# HAE_Power_Protection.net
KiCad netlist of a schematic drawn in Altium Designer
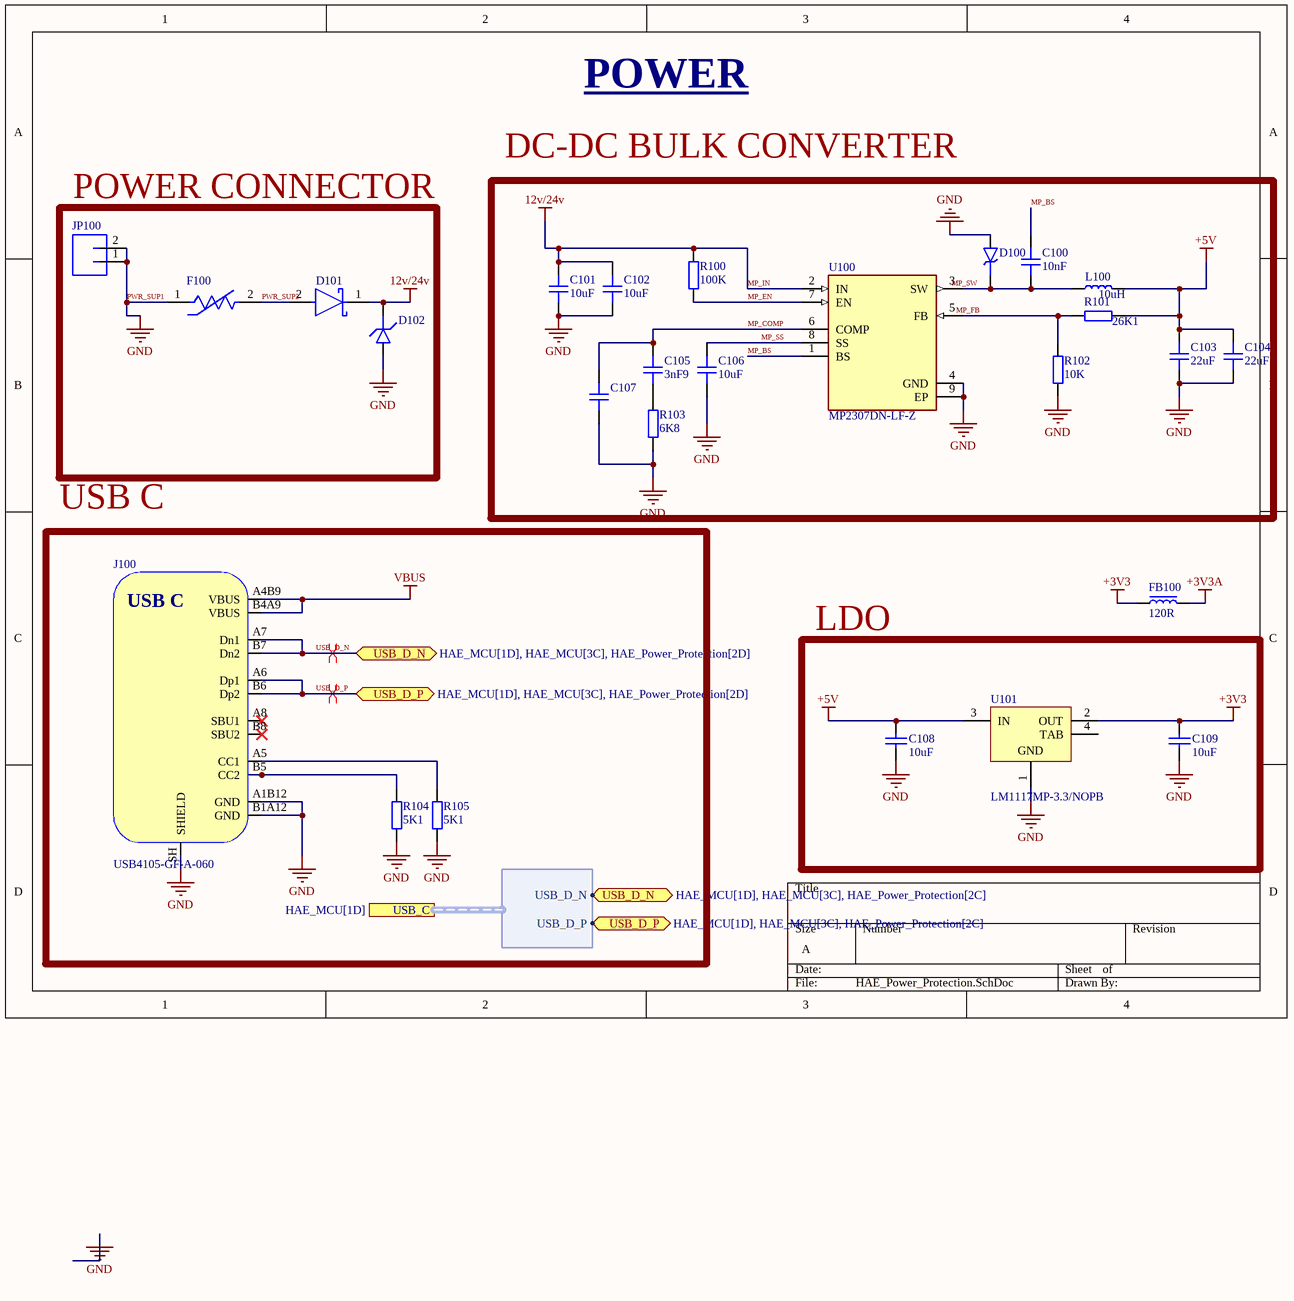
[diagram p0: HAE_Power_Protection.SchDoc]

(export (version "E")
  (design (tool "Eeschema 10.0.6"))
  (components
    (comp (ref "C100")
      (value "10nF")
      (footprint "CAP_0603")
      (description "Capacitor SMD 0603")
      (libsource (lib "PhilsLab_Library") (part "CAP_0603"))
    )
    (comp (ref "C101")
      (value "10uF")
      (footprint "CAP_0603")
      (description "Capacitor SMD 0603")
      (libsource (lib "PhilsLab_Library") (part "CAP_0603"))
    )
    (comp (ref "C102")
      (value "10uF")
      (footprint "CAP_0603")
      (description "Capacitor SMD 0603")
      (libsource (lib "PhilsLab_Library") (part "CAP_0603"))
    )
    (comp (ref "C103")
      (value "22uF")
      (footprint "CAP_0603")
      (description "Capacitor SMD 0603")
      (libsource (lib "PhilsLab_Library") (part "CAP_0603"))
    )
    (comp (ref "C104")
      (value "22uF")
      (footprint "CAP_0603")
      (description "Capacitor SMD 0603")
      (libsource (lib "PhilsLab_Library") (part "CAP_0603"))
    )
    (comp (ref "C105")
      (value "3nF9")
      (footprint "CAP_0603")
      (description "Capacitor SMD 0603")
      (libsource (lib "PhilsLab_Library") (part "CAP_0603"))
    )
    (comp (ref "C106")
      (value "10uF")
      (footprint "CAP_0603")
      (description "Capacitor SMD 0603")
      (libsource (lib "PhilsLab_Library") (part "CAP_0603"))
    )
    (comp (ref "C107")
      (value "10uF")
      (footprint "CAP_0603")
      (description "Capacitor SMD 0603")
      (libsource (lib "PhilsLab_Library") (part "CAP_0603"))
    )
    (comp (ref "C108")
      (value "10uF")
      (footprint "CAPC2014X60X15NL20")
      (description "TACH106M010XTA")
      (fields (field (name "MANUFACTURER") "AVX Interconnect / Elco"))
      (libsource (lib "Altium Content Vault") (part "CAP"))
    )
    (comp (ref "C109")
      (value "10uF")
      (footprint "CAPC2014X60X15NL20")
      (description "TACH106M010XTA")
      (fields (field (name "MANUFACTURER") "AVX Interconnect / Elco"))
      (libsource (lib "Altium Content Vault") (part "CAP"))
    )
    (comp (ref "D100")
      (value "D_ZENER_SOD_323")
      (footprint "SOD-323")
      (description "Diode Zener SMD SOD-323")
      (libsource (lib "PhilsLab_Library") (part "D_ZENER_SOD_323"))
    )
    (comp (ref "D101")
      (value "SS34-E3/9AT")
      (footprint "FP-SMC-MFG")
      (description "DIODE SCHOTTKY 40V 3A DO214AB")
      (libsource (lib "Altium Content Vault") (part "c1678fac7984e62e0809fbf79c06691"))
    )
    (comp (ref "D102")
      (value "D_TVS_0402")
      (footprint "D_0402")
      (description "Diode TVS / ESD 0402")
      (libsource (lib "PhilsLab_Library") (part "D_TVS_0402"))
    )
    (comp (ref "F100")
      (value "MF-PSMF020X-2")
      (footprint "FP-MF-PSMF-MFG")
      (description "PTC RESET FUSE 9V 200MA 0805")
      (fields
        (field (name "MANUFACTURER") "Bourns")
        (field (name "OCTOPART") "https://octopart.com/mf-psmf020x-2-bourns-7483437")
      )
      (libsource (lib "Altium Content Vault") (part "3b148a6ebabc5fb4d708a66c052d352"))
    )
    (comp (ref "FB100")
      (value "120R")
      (footprint "FB_0603")
      (description "Ferrite Bead SMD 0603")
      (libsource (lib "Schematic-Lib-PhilsLab") (part "FB_0603"))
    )
    (comp (ref "J100")
      (value "USB4105-GF-A-060")
      (footprint "USB4105-GF-A-060")
      (description "USB Connector Type C SMT 12 Pin")
      (fields (field (name "MANUFACTURER") "GCT"))
      (libsource (lib "PhilsLab_Library") (part "USB4105-GF-A-060"))
    )
    (comp (ref "JP100")
      (value "MOLEX_MICROFIT_2_SMD_HORZ")
      (footprint "MOLEX-MICROFIT-2-SMD-HORZ")
      (fields (field (name "MANUFACTURER") "Molex") (field (name "PARTNUMBER") "43650-0212"))
      (libsource (lib "HAE_Schlib1") (part "MOLEX_MICROFIT_2_SMD_HORZ"))
    )
    (comp (ref "L100")
      (value "10uH")
      (footprint "IND_0603")
      (description "Inductor SMD 0603")
      (libsource (lib "PhilsLab_Library") (part "IND_0603"))
    )
    (comp (ref "R100")
      (value "100K")
      (footprint "RES_0603")
      (description "Resistor SMD 0603")
      (libsource (lib "PhilsLab_Library") (part "RES_0603"))
    )
    (comp (ref "R101")
      (value "26K1")
      (footprint "RES_0603")
      (description "Resistor SMD 0603")
      (libsource (lib "PhilsLab_Library") (part "RES_0603"))
    )
    (comp (ref "R102")
      (value "10K")
      (footprint "RES_0603")
      (description "Resistor SMD 0603")
      (libsource (lib "PhilsLab_Library") (part "RES_0603"))
    )
    (comp (ref "R103")
      (value "6K8")
      (footprint "RES_0603")
      (description "Resistor SMD 0603")
      (libsource (lib "PhilsLab_Library") (part "RES_0603"))
    )
    (comp (ref "R104")
      (value "5K1")
      (footprint "RES_0402")
      (description "Resistor SMD 0402")
      (libsource (lib "PhilsLab_Library") (part "RES_0402"))
    )
    (comp (ref "R105")
      (value "5K1")
      (footprint "RES_0402")
      (description "Resistor SMD 0402")
      (libsource (lib "PhilsLab_Library") (part "RES_0402"))
    )
    (comp (ref "U100")
      (value "MP2307DN-LF-Z")
      (footprint "SOIC127P600X170-9N")
      (fields (field (name "MF") "Monolithic Power"))
      (libsource (lib "HAE_Schlib1") (part "MP2307DN-LF-Z"))
    )
    (comp (ref "U101")
      (value "LM1117MP-3.3/NOPB")
      (footprint "DCY0004A_L")
      (description "800mA Low-Dropout Linear Regulator, 4-pin SOT-223, Pb-Free")
      (fields (field (name "MANUFACTURER") "Texas Instruments"))
      (libsource (lib "Altium Content Vault") (part "PM-REG-LM1086-SOT4"))
    )
  )
  (nets
    (net (code "2") (name "+3V3") (class "Default")
      (node (ref "C109") (pin "2") (pinfunction "2_2") (pintype "passive"))
      (node (ref "FB100") (pin "1") (pinfunction "1_1") (pintype "passive"))
      (node (ref "U101") (pin "2") (pinfunction "OUT_2") (pintype "power_in"))
    )
    (net (code "3") (name "+3V3A") (class "Default")
      (node (ref "FB100") (pin "2") (pinfunction "2_2") (pintype "passive"))
    )
    (net (code "4") (name "+5V") (class "Default")
      (node (ref "C103") (pin "2") (pinfunction "2_2") (pintype "passive"))
      (node (ref "C104") (pin "2") (pinfunction "2_2") (pintype "passive"))
      (node (ref "C108") (pin "2") (pinfunction "2_2") (pintype "passive"))
      (node (ref "L100") (pin "2") (pinfunction "2_2") (pintype "passive"))
      (node (ref "R101") (pin "1") (pinfunction "1_1") (pintype "passive"))
      (node (ref "U101") (pin "3") (pinfunction "IN_3") (pintype "power_in"))
    )
    (net (code "5") (name "/MP_BS") (class "Default")
      (node (ref "C100") (pin "1") (pinfunction "1_1") (pintype "passive"))
      (node (ref "U100") (pin "1") (pinfunction "BS_1") (pintype "passive"))
    )
    (net (code "6") (name "/MP_COMP") (class "Default")
      (node (ref "C105") (pin "2") (pinfunction "2_2") (pintype "passive"))
      (node (ref "C107") (pin "2") (pinfunction "2_2") (pintype "passive"))
      (node (ref "U100") (pin "6") (pinfunction "COMP_6") (pintype "passive"))
    )
    (net (code "7") (name "/MP_EN") (class "Default")
      (node (ref "R100") (pin "1") (pinfunction "1_1") (pintype "passive"))
      (node (ref "U100") (pin "7") (pinfunction "EN_7") (pintype "input"))
    )
    (net (code "8") (name "/MP_FB") (class "Default")
      (node (ref "R101") (pin "2") (pinfunction "2_2") (pintype "passive"))
      (node (ref "R102") (pin "2") (pinfunction "2_2") (pintype "passive"))
      (node (ref "U100") (pin "5") (pinfunction "FB_5") (pintype "input"))
    )
    (net (code "9") (name "/MP_SS") (class "Default")
      (node (ref "C106") (pin "2") (pinfunction "2_2") (pintype "passive"))
      (node (ref "U100") (pin "8") (pinfunction "SS_8") (pintype "passive"))
    )
    (net (code "10") (name "/MP_SW") (class "Default")
      (node (ref "C100") (pin "2") (pinfunction "2_2") (pintype "passive"))
      (node (ref "D100") (pin "K") (pinfunction "K_K") (pintype "passive"))
      (node (ref "L100") (pin "1") (pinfunction "1_1") (pintype "passive"))
      (node (ref "U100") (pin "3") (pinfunction "SW_3") (pintype "output"))
    )
    (net (code "11") (name "/PWR_SUP2") (class "Default")
      (node (ref "D101") (pin "2") (pinfunction "A_2") (pintype "passive"))
      (node (ref "F100") (pin "2") (pinfunction "2_2") (pintype "passive"))
    )
    (net (code "12") (name "/USB_D_N") (class "Default")
      (node (ref "J100") (pin "A7") (pinfunction "Dn1_A7") (pintype "passive"))
      (node (ref "J100") (pin "B7") (pinfunction "Dn2_B7") (pintype "passive"))
    )
    (net (code "13") (name "/USB_D_P") (class "Default")
      (node (ref "J100") (pin "A6") (pinfunction "Dp1_A6") (pintype "passive"))
      (node (ref "J100") (pin "B6") (pinfunction "Dp2_B6") (pintype "passive"))
    )
    (net (code "15") (name "12v{slash}24v") (class "Default")
      (node (ref "C101") (pin "2") (pinfunction "2_2") (pintype "passive"))
      (node (ref "C102") (pin "2") (pinfunction "2_2") (pintype "passive"))
      (node (ref "D101") (pin "1") (pinfunction "C_1") (pintype "passive"))
      (node (ref "D102") (pin "K") (pinfunction "K_K") (pintype "passive"))
      (node (ref "R100") (pin "2") (pinfunction "2_2") (pintype "passive"))
      (node (ref "U100") (pin "2") (pinfunction "IN_2") (pintype "input"))
    )
    (net (code "16") (name "GND") (class "Default")
      (node (ref "C101") (pin "1") (pinfunction "1_1") (pintype "passive"))
      (node (ref "C102") (pin "1") (pinfunction "1_1") (pintype "passive"))
      (node (ref "C103") (pin "1") (pinfunction "1_1") (pintype "passive"))
      (node (ref "C104") (pin "1") (pinfunction "1_1") (pintype "passive"))
      (node (ref "C106") (pin "1") (pinfunction "1_1") (pintype "passive"))
      (node (ref "C107") (pin "1") (pinfunction "1_1") (pintype "passive"))
      (node (ref "C108") (pin "1") (pinfunction "1_1") (pintype "passive"))
      (node (ref "C109") (pin "1") (pinfunction "1_1") (pintype "passive"))
      (node (ref "D100") (pin "A") (pinfunction "A_A") (pintype "passive"))
      (node (ref "D102") (pin "A") (pinfunction "A_A") (pintype "passive"))
      (node (ref "F100") (pin "1") (pinfunction "1_1") (pintype "passive"))
      (node (ref "J100") (pin "A1B12") (pinfunction "GND_A1B12") (pintype "passive"))
      (node (ref "J100") (pin "B1A12") (pinfunction "GND_B1A12") (pintype "passive"))
      (node (ref "J100") (pin "SH") (pinfunction "SHIELD_SH") (pintype "passive"))
      (node (ref "JP100") (pin "1") (pinfunction "1_1") (pintype "passive"))
      (node (ref "JP100") (pin "2") (pinfunction "2_2") (pintype "passive"))
      (node (ref "R102") (pin "1") (pinfunction "1_1") (pintype "passive"))
      (node (ref "R103") (pin "1") (pinfunction "1_1") (pintype "passive"))
      (node (ref "R104") (pin "1") (pinfunction "1_1") (pintype "passive"))
      (node (ref "R105") (pin "1") (pinfunction "1_1") (pintype "passive"))
      (node (ref "U100") (pin "4") (pinfunction "GND_4") (pintype "power_in"))
      (node (ref "U100") (pin "9") (pinfunction "EP_9") (pintype "power_in"))
      (node (ref "U101") (pin "1") (pinfunction "GND_1") (pintype "power_in"))
    )
    (net (code "17") (name "Net-(C105-Pad1)") (class "Default")
      (node (ref "C105") (pin "1") (pinfunction "1_1") (pintype "passive"))
      (node (ref "R103") (pin "2") (pinfunction "2_2") (pintype "passive"))
    )
    (net (code "18") (name "Net-(J100-CC1)") (class "Default")
      (node (ref "J100") (pin "A5") (pinfunction "CC1_A5") (pintype "passive"))
      (node (ref "R105") (pin "2") (pinfunction "2_2") (pintype "passive"))
    )
    (net (code "19") (name "Net-(J100-CC2)") (class "Default")
      (node (ref "J100") (pin "B5") (pinfunction "CC2_B5") (pintype "passive"))
      (node (ref "R104") (pin "2") (pinfunction "2_2") (pintype "passive"))
    )
    (net (code "20") (name "VBUS") (class "Default")
      (node (ref "J100") (pin "A4B9") (pinfunction "VBUS_A4B9") (pintype "passive"))
      (node (ref "J100") (pin "B4A9") (pinfunction "VBUS_B4A9") (pintype "passive"))
    )
    (net (code "21") (name "unconnected-(J100-SBU1-PadA8)") (class "Default")
      (node (ref "J100") (pin "A8") (pinfunction "SBU1_A8") (pintype "passive+no_connect"))
    )
    (net (code "22") (name "unconnected-(J100-SBU2-PadB8)") (class "Default")
      (node (ref "J100") (pin "B8") (pinfunction "SBU2_B8") (pintype "passive+no_connect"))
    )
    (net (code "23") (name "unconnected-(U101-TAB-Pad4)") (class "Default")
      (node (ref "U101") (pin "4") (pinfunction "TAB_4") (pintype "power_in"))
    )
  )
)
